# Serf_G2553.net
KiCad netlist of a schematic drawn in EAGLE
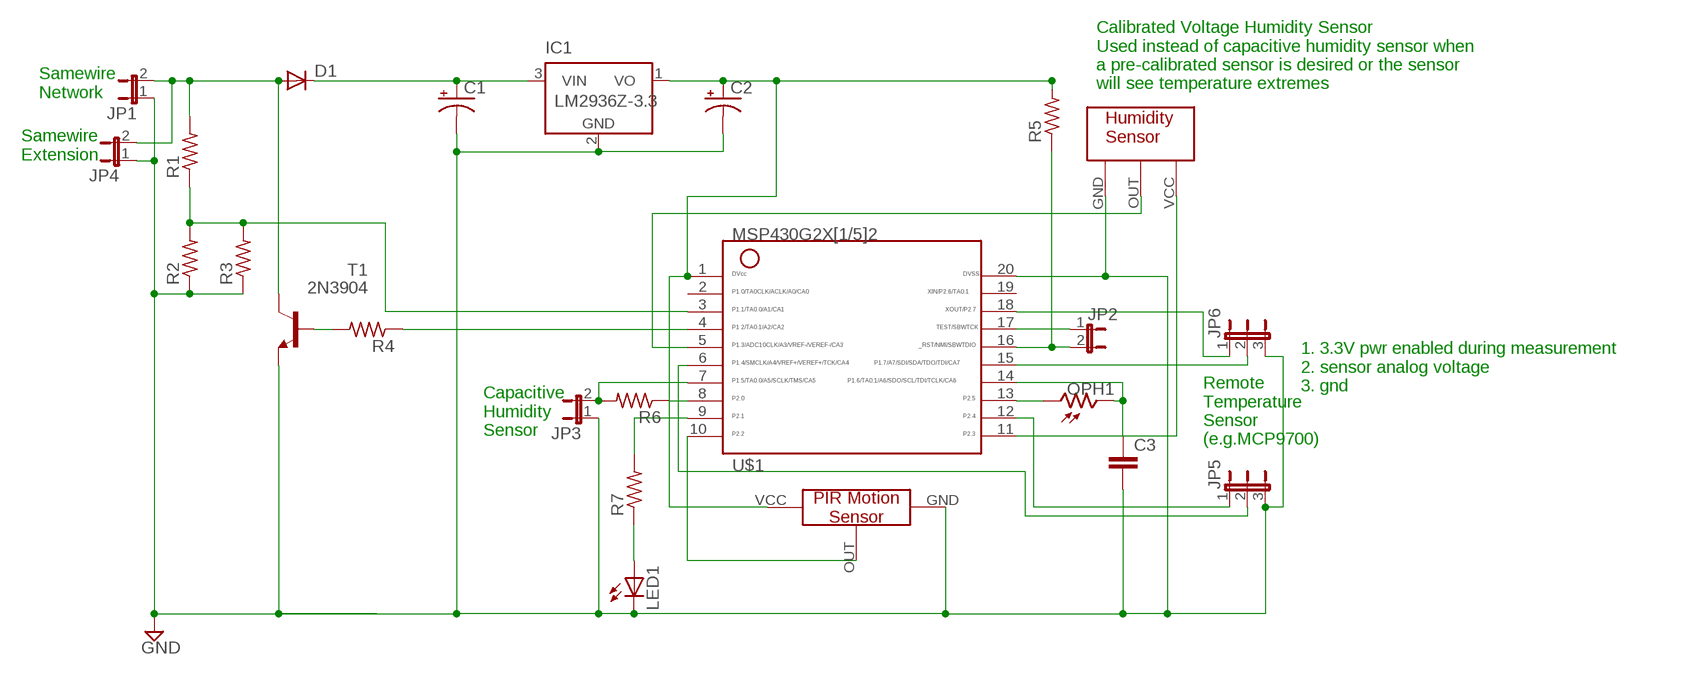
[diagram p0: schematic, sheet 1]

(export (version "E")
  (design (tool "Eeschema 10.0.6"))
  (components
    (comp (ref "C1")
      (value "CPOL-USE2.5-6")
      (footprint "eagle-import:E2,5-6")
      (libsource (lib "eagle-import") (part "CPOL-USE2.5-6"))
    )
    (comp (ref "C2")
      (value "CPOL-USE2.5-6")
      (footprint "eagle-import:E2,5-6")
      (libsource (lib "eagle-import") (part "CPOL-USE2.5-6"))
    )
    (comp (ref "C3")
      (value "C7.5/3")
      (footprint "eagle-import:C7.5B3")
      (libsource (lib "eagle-import") (part "C7.5/3"))
    )
    (comp (ref "D1")
      (value "1N4148DO35-7")
      (footprint "eagle-import:DO35-7")
      (libsource (lib "eagle-import") (part "1N4148DO35-7"))
    )
    (comp (ref "IC1")
      (value "LM2936Z-3.3")
      (footprint "eagle-import:TO92")
      (fields (field (name "MF") "NATIONAL SEMICONDUCTOR") (field (name "MPN") "LM2936Z-3.3/NOPB"))
      (libsource (lib "eagle-import") (part "LM2936?Z-3.3"))
    )
    (comp (ref "JP1")
      (value "JP1E")
      (footprint "eagle-import:JP1")
      (libsource (lib "eagle-import") (part "JP1E"))
    )
    (comp (ref "JP2")
      (value "JP1E")
      (footprint "eagle-import:JP1")
      (libsource (lib "eagle-import") (part "JP1E"))
    )
    (comp (ref "JP3")
      (value "JP1E")
      (footprint "eagle-import:JP1")
      (libsource (lib "eagle-import") (part "JP1E"))
    )
    (comp (ref "JP4")
      (value "JP1E")
      (footprint "eagle-import:JP1")
      (libsource (lib "eagle-import") (part "JP1E"))
    )
    (comp (ref "JP5")
      (value "JP2E")
      (footprint "eagle-import:JP2")
      (libsource (lib "eagle-import") (part "JP2E"))
    )
    (comp (ref "JP6")
      (value "JP2E")
      (footprint "eagle-import:JP2")
      (libsource (lib "eagle-import") (part "JP2E"))
    )
    (comp (ref "LED1")
      (value "LED3MM")
      (footprint "eagle-import:LED3MM")
      (libsource (lib "eagle-import") (part "LED3MM"))
    )
    (comp (ref "OPH1")
      (value "VT90N1")
      (footprint "eagle-import:VT900")
      (libsource (lib "eagle-import") (part "VT90N1"))
    )
    (comp (ref "R1")
      (value "R-US_0204/2V")
      (footprint "eagle-import:0204V")
      (libsource (lib "eagle-import") (part "R-US_0204/2V"))
    )
    (comp (ref "R2")
      (value "R-US_0204/2V")
      (footprint "eagle-import:0204V")
      (libsource (lib "eagle-import") (part "R-US_0204/2V"))
    )
    (comp (ref "R3")
      (value "R-US_0204/2V")
      (footprint "eagle-import:0204V")
      (libsource (lib "eagle-import") (part "R-US_0204/2V"))
    )
    (comp (ref "R4")
      (value "R-US_0204/2V")
      (footprint "eagle-import:0204V")
      (libsource (lib "eagle-import") (part "R-US_0204/2V"))
    )
    (comp (ref "R5")
      (value "R-US_0204/2V")
      (footprint "eagle-import:0204V")
      (libsource (lib "eagle-import") (part "R-US_0204/2V"))
    )
    (comp (ref "R6")
      (value "R-US_0204/2V")
      (footprint "eagle-import:0204V")
      (libsource (lib "eagle-import") (part "R-US_0204/2V"))
    )
    (comp (ref "R7")
      (value "R-US_0204/2V")
      (footprint "eagle-import:0204V")
      (libsource (lib "eagle-import") (part "R-US_0204/2V"))
    )
    (comp (ref "T1")
      (value "2N3904")
      (footprint "eagle-import:TO92")
      (libsource (lib "eagle-import") (part "2N3904"))
    )
    (comp (ref "U$1")
      (value "G2X[1/5]2---N20")
      (footprint "eagle-import:N20")
      (libsource (lib "eagle-import") (part "G2X[1/5]2---N20"))
    )
    (comp (ref "U$2")
      (value "PANASONIC_PIR")
      (footprint "eagle-import:PANASONIC_PIR")
      (libsource (lib "eagle-import") (part "PANASONIC_PIR"))
    )
    (comp (ref "U$3")
      (value "HIH-5030")
      (footprint "eagle-import:HIH-530")
      (libsource (lib "eagle-import") (part "HIH-5030"))
    )
  )
  (nets
    (net (code "1") (name "GND") (class "Default")
      (node (ref "C1") (pin "-") (pinfunction "-_-") (pintype "passive"))
      (node (ref "C2") (pin "-") (pinfunction "-_-") (pintype "passive"))
      (node (ref "C3") (pin "2") (pinfunction "2_2") (pintype "passive"))
      (node (ref "IC1") (pin "2") (pinfunction "GND_2") (pintype "passive"))
      (node (ref "JP1") (pin "1") (pinfunction "1_1") (pintype "passive"))
      (node (ref "JP3") (pin "1") (pinfunction "1_1") (pintype "passive"))
      (node (ref "JP4") (pin "1") (pinfunction "1_1") (pintype "passive"))
      (node (ref "JP5") (pin "3") (pinfunction "3_3") (pintype "passive"))
      (node (ref "JP6") (pin "3") (pinfunction "3_3") (pintype "passive"))
      (node (ref "LED1") (pin "K") (pinfunction "C_K") (pintype "passive"))
      (node (ref "R2") (pin "1") (pinfunction "1_1") (pintype "passive"))
      (node (ref "R3") (pin "1") (pinfunction "1_1") (pintype "passive"))
      (node (ref "T1") (pin "3") (pinfunction "E_3") (pintype "passive"))
      (node (ref "U$1") (pin "20") (pinfunction "20_20") (pintype "bidirectional"))
      (node (ref "U$2") (pin "GND") (pinfunction "GND_GND") (pintype "power_in"))
      (node (ref "U$3") (pin "GND") (pinfunction "GND_GND") (pintype "power_in"))
    )
    (net (code "2") (name "Net-(C3-Pad1)") (class "Default")
      (node (ref "C3") (pin "1") (pinfunction "1_1") (pintype "passive"))
      (node (ref "OPH1") (pin "2") (pinfunction "2_2") (pintype "passive"))
      (node (ref "U$1") (pin "14") (pinfunction "14_14") (pintype "bidirectional"))
    )
    (net (code "3") (name "Net-(IC1-VIN)") (class "Default")
      (node (ref "C1") (pin "+") (pinfunction "+_+") (pintype "passive"))
      (node (ref "D1") (pin "C") (pinfunction "C_C") (pintype "passive"))
      (node (ref "IC1") (pin "3") (pinfunction "VIN_3") (pintype "input"))
    )
    (net (code "4") (name "Net-(IC1-VO)") (class "Default")
      (node (ref "C2") (pin "+") (pinfunction "+_+") (pintype "passive"))
      (node (ref "IC1") (pin "1") (pinfunction "VO_1") (pintype "passive"))
      (node (ref "R5") (pin "2") (pinfunction "2_2") (pintype "passive"))
      (node (ref "U$1") (pin "1") (pinfunction "1_1") (pintype "bidirectional"))
      (node (ref "U$2") (pin "VCC") (pinfunction "VCC_VCC") (pintype "power_in"))
    )
    (net (code "5") (name "Net-(JP2-Pad1)") (class "Default")
      (node (ref "JP2") (pin "1") (pinfunction "1_1") (pintype "passive"))
      (node (ref "U$1") (pin "17") (pinfunction "17_17") (pintype "bidirectional"))
    )
    (net (code "6") (name "Net-(JP2-Pad2)") (class "Default")
      (node (ref "JP2") (pin "2") (pinfunction "2_2") (pintype "passive"))
      (node (ref "R5") (pin "1") (pinfunction "1_1") (pintype "passive"))
      (node (ref "U$1") (pin "16") (pinfunction "16_16") (pintype "bidirectional"))
    )
    (net (code "7") (name "Net-(JP3-Pad2)") (class "Default")
      (node (ref "JP3") (pin "2") (pinfunction "2_2") (pintype "passive"))
      (node (ref "R6") (pin "2") (pinfunction "2_2") (pintype "passive"))
      (node (ref "U$1") (pin "7") (pinfunction "7_7") (pintype "bidirectional"))
    )
    (net (code "8") (name "Net-(JP5-Pad1)") (class "Default")
      (node (ref "JP5") (pin "1") (pinfunction "1_1") (pintype "passive"))
      (node (ref "U$1") (pin "12") (pinfunction "12_12") (pintype "bidirectional"))
    )
    (net (code "9") (name "Net-(JP5-Pad2)") (class "Default")
      (node (ref "JP5") (pin "2") (pinfunction "2_2") (pintype "passive"))
      (node (ref "U$1") (pin "6") (pinfunction "6_6") (pintype "bidirectional"))
    )
    (net (code "10") (name "Net-(JP6-Pad1)") (class "Default")
      (node (ref "JP6") (pin "1") (pinfunction "1_1") (pintype "passive"))
      (node (ref "U$1") (pin "18") (pinfunction "18_18") (pintype "bidirectional"))
    )
    (net (code "11") (name "Net-(JP6-Pad2)") (class "Default")
      (node (ref "JP6") (pin "2") (pinfunction "2_2") (pintype "passive"))
      (node (ref "U$1") (pin "15") (pinfunction "15_15") (pintype "bidirectional"))
    )
    (net (code "12") (name "Net-(LED1-PadA)") (class "Default")
      (node (ref "LED1") (pin "A") (pinfunction "A_A") (pintype "passive"))
      (node (ref "R7") (pin "1") (pinfunction "1_1") (pintype "passive"))
    )
    (net (code "13") (name "Net-(OPH1-Pad1)") (class "Default")
      (node (ref "OPH1") (pin "1") (pinfunction "1_1") (pintype "passive"))
      (node (ref "U$1") (pin "13") (pinfunction "13_13") (pintype "bidirectional"))
    )
    (net (code "14") (name "Net-(R1-Pad1)") (class "Default")
      (node (ref "R1") (pin "1") (pinfunction "1_1") (pintype "passive"))
      (node (ref "R2") (pin "2") (pinfunction "2_2") (pintype "passive"))
      (node (ref "R3") (pin "2") (pinfunction "2_2") (pintype "passive"))
      (node (ref "U$1") (pin "3") (pinfunction "3_3") (pintype "bidirectional"))
    )
    (net (code "15") (name "Net-(R4-Pad1)") (class "Default")
      (node (ref "R4") (pin "1") (pinfunction "1_1") (pintype "passive"))
      (node (ref "U$1") (pin "4") (pinfunction "4_4") (pintype "bidirectional"))
    )
    (net (code "16") (name "Net-(R6-Pad1)") (class "Default")
      (node (ref "R6") (pin "1") (pinfunction "1_1") (pintype "passive"))
      (node (ref "U$1") (pin "8") (pinfunction "8_8") (pintype "bidirectional"))
    )
    (net (code "17") (name "Net-(R7-Pad2)") (class "Default")
      (node (ref "R7") (pin "2") (pinfunction "2_2") (pintype "passive"))
      (node (ref "U$1") (pin "9") (pinfunction "9_9") (pintype "bidirectional"))
    )
    (net (code "18") (name "Net-(T1-B)") (class "Default")
      (node (ref "R4") (pin "2") (pinfunction "2_2") (pintype "passive"))
      (node (ref "T1") (pin "2") (pinfunction "B_2") (pintype "passive"))
    )
    (net (code "19") (name "Net-(T1-C)") (class "Default")
      (node (ref "D1") (pin "A") (pinfunction "A_A") (pintype "passive"))
      (node (ref "JP1") (pin "2") (pinfunction "2_2") (pintype "passive"))
      (node (ref "JP4") (pin "2") (pinfunction "2_2") (pintype "passive"))
      (node (ref "R1") (pin "2") (pinfunction "2_2") (pintype "passive"))
      (node (ref "T1") (pin "1") (pinfunction "C_1") (pintype "passive"))
    )
    (net (code "20") (name "Net-(U$1-Pad5)") (class "Default")
      (node (ref "U$1") (pin "5") (pinfunction "5_5") (pintype "bidirectional"))
      (node (ref "U$3") (pin "OUT") (pinfunction "OUT_OUT") (pintype "output"))
    )
    (net (code "21") (name "Net-(U$1-Pad10)") (class "Default")
      (node (ref "U$1") (pin "10") (pinfunction "10_10") (pintype "bidirectional"))
      (node (ref "U$2") (pin "OUT") (pinfunction "OUT_OUT") (pintype "open_collector"))
    )
    (net (code "22") (name "Net-(U$1-Pad11)") (class "Default")
      (node (ref "U$1") (pin "11") (pinfunction "11_11") (pintype "bidirectional"))
      (node (ref "U$3") (pin "VCC") (pinfunction "VCC_VCC") (pintype "power_in"))
    )
    (net (code "23") (name "unconnected-(U$1-Pad2)") (class "Default")
      (node (ref "U$1") (pin "2") (pinfunction "2_2") (pintype "bidirectional"))
    )
    (net (code "24") (name "unconnected-(U$1-Pad19)") (class "Default")
      (node (ref "U$1") (pin "19") (pinfunction "19_19") (pintype "bidirectional"))
    )
  )
)
